# TemperatureSensor.net
KiCad netlist of a schematic drawn in EAGLE
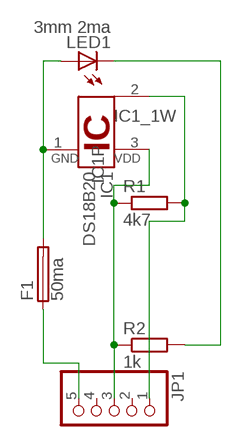
[diagram p0: schematic, sheet 1]

(export (version "E")
  (design (tool "Eeschema 10.0.6"))
  (components
    (comp (ref "F1")
      (value "50ma")
      (footprint "eagle-import:MF-SMDF050")
      (libsource (lib "eagle-import") (part "MF-SMDF050"))
    )
    (comp (ref "IC1")
      (value "DS18B20")
      (footprint "eagle-import:TO92-")
      (libsource (lib "eagle-import") (part "DS18B20"))
    )
    (comp (ref "JP1")
      (value "PINHD-1X5/90")
      (footprint "eagle-import:1X05_90")
      (libsource (lib "eagle-import") (part "PINHD-1X5/90"))
    )
    (comp (ref "LED1")
      (value "3mm 2ma")
      (footprint "eagle-import:LED3MM")
      (fields (field (name "MF") "VISHAY SEMICONDUCTOR"))
      (libsource (lib "eagle-import") (part "TLLY4400"))
    )
    (comp (ref "R1")
      (value "4k7")
      (footprint "eagle-import:R1206")
      (libsource (lib "eagle-import") (part "R-EU_R1206"))
    )
    (comp (ref "R2")
      (value "1k")
      (footprint "eagle-import:R1206")
      (libsource (lib "eagle-import") (part "R-EU_R1206"))
    )
  )
  (nets
    (net (code "1") (name "Net-(F1-Pad1)") (class "Default")
      (node (ref "F1") (pin "1") (pinfunction "1_1") (pintype "passive"))
      (node (ref "JP1") (pin "5") (pinfunction "5_5") (pintype "passive"))
    )
    (net (code "2") (name "Net-(IC1B-GND)") (class "Default")
      (node (ref "F1") (pin "2") (pinfunction "2_2") (pintype "passive"))
      (node (ref "IC1") (pin "1") (pinfunction "GND_1") (pintype "power_in"))
      (node (ref "LED1") (pin "A") (pinfunction "A_A") (pintype "passive"))
    )
    (net (code "3") (name "Net-(IC1B-VDD)") (class "Default")
      (node (ref "IC1") (pin "3") (pinfunction "VDD_3") (pintype "power_in"))
      (node (ref "JP1") (pin "3") (pinfunction "3_3") (pintype "passive"))
      (node (ref "R1") (pin "1") (pinfunction "1_1") (pintype "passive"))
      (node (ref "R2") (pin "1") (pinfunction "1_1") (pintype "passive"))
    )
    (net (code "4") (name "Net-(IC1C-1W)") (class "Default")
      (node (ref "IC1") (pin "2") (pinfunction "1W_2") (pintype "power_in"))
      (node (ref "JP1") (pin "1") (pinfunction "1_1") (pintype "passive"))
      (node (ref "R1") (pin "2") (pinfunction "2_2") (pintype "passive"))
    )
    (net (code "5") (name "Net-(LED1-C)") (class "Default")
      (node (ref "LED1") (pin "K") (pinfunction "C_K") (pintype "passive"))
      (node (ref "R2") (pin "2") (pinfunction "2_2") (pintype "passive"))
    )
    (net (code "6") (name "unconnected-(JP1-Pad2)") (class "Default")
      (node (ref "JP1") (pin "2") (pinfunction "2_2") (pintype "passive"))
    )
    (net (code "7") (name "unconnected-(JP1-Pad4)") (class "Default")
      (node (ref "JP1") (pin "4") (pinfunction "4_4") (pintype "passive"))
    )
  )
)
